# energy-management-driver-175_v2.net
KiCad netlist of a schematic drawn in EAGLE
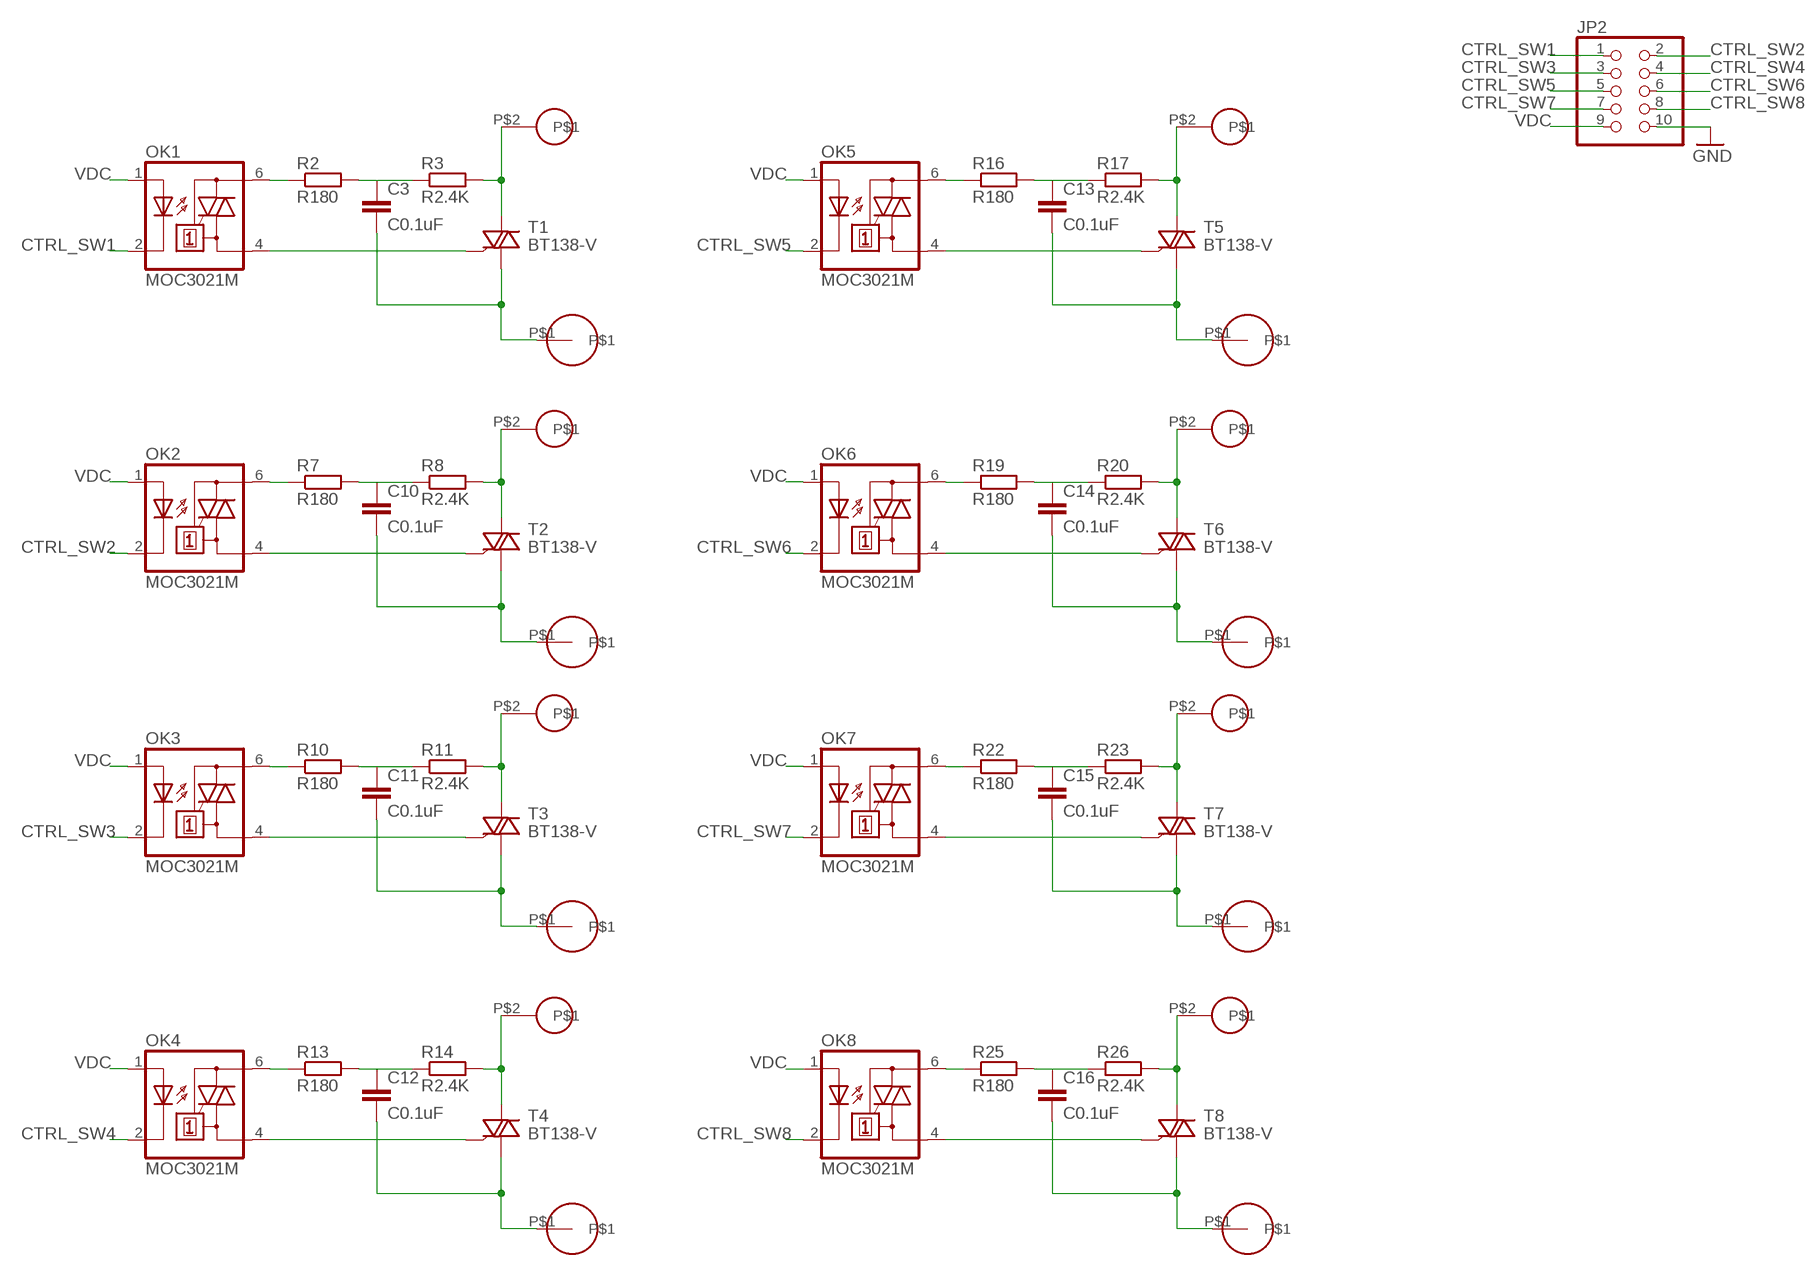
[diagram p0: schematic, sheet 1]

(export (version "E")
  (design (tool "Eeschema 10.0.6"))
  (components
    (comp (ref "C3")
      (value "C0.1uF")
      (footprint "eagle-import:C0805")
      (libsource (lib "eagle-import") (part "C-EUC0805"))
    )
    (comp (ref "C10")
      (value "C0.1uF")
      (footprint "eagle-import:C0805")
      (libsource (lib "eagle-import") (part "C-EUC0805"))
    )
    (comp (ref "C11")
      (value "C0.1uF")
      (footprint "eagle-import:C0805")
      (libsource (lib "eagle-import") (part "C-EUC0805"))
    )
    (comp (ref "C12")
      (value "C0.1uF")
      (footprint "eagle-import:C0805")
      (libsource (lib "eagle-import") (part "C-EUC0805"))
    )
    (comp (ref "C13")
      (value "C0.1uF")
      (footprint "eagle-import:C0805")
      (libsource (lib "eagle-import") (part "C-EUC0805"))
    )
    (comp (ref "C14")
      (value "C0.1uF")
      (footprint "eagle-import:C0805")
      (libsource (lib "eagle-import") (part "C-EUC0805"))
    )
    (comp (ref "C15")
      (value "C0.1uF")
      (footprint "eagle-import:C0805")
      (libsource (lib "eagle-import") (part "C-EUC0805"))
    )
    (comp (ref "C16")
      (value "C0.1uF")
      (footprint "eagle-import:C0805")
      (libsource (lib "eagle-import") (part "C-EUC0805"))
    )
    (comp (ref "JP2")
      (value "PINHD-2X5")
      (footprint "eagle-import:2X05")
      (libsource (lib "eagle-import") (part "PINHD-2X5"))
    )
    (comp (ref "OK1")
      (value "MOC3021M")
      (footprint "eagle-import:DIL06")
      (fields (field (name "MF") "FAIRCHILD SEMICONDUCTOR") (field (name "MPN") "MOC3021-M"))
      (libsource (lib "eagle-import") (part "MOC30M21"))
    )
    (comp (ref "OK2")
      (value "MOC3021M")
      (footprint "eagle-import:DIL06")
      (fields (field (name "MF") "FAIRCHILD SEMICONDUCTOR") (field (name "MPN") "MOC3021-M"))
      (libsource (lib "eagle-import") (part "MOC30M21"))
    )
    (comp (ref "OK3")
      (value "MOC3021M")
      (footprint "eagle-import:DIL06")
      (fields (field (name "MF") "FAIRCHILD SEMICONDUCTOR") (field (name "MPN") "MOC3021-M"))
      (libsource (lib "eagle-import") (part "MOC30M21"))
    )
    (comp (ref "OK4")
      (value "MOC3021M")
      (footprint "eagle-import:DIL06")
      (fields (field (name "MF") "FAIRCHILD SEMICONDUCTOR") (field (name "MPN") "MOC3021-M"))
      (libsource (lib "eagle-import") (part "MOC30M21"))
    )
    (comp (ref "OK5")
      (value "MOC3021M")
      (footprint "eagle-import:DIL06")
      (fields (field (name "MF") "FAIRCHILD SEMICONDUCTOR") (field (name "MPN") "MOC3021-M"))
      (libsource (lib "eagle-import") (part "MOC30M21"))
    )
    (comp (ref "OK6")
      (value "MOC3021M")
      (footprint "eagle-import:DIL06")
      (fields (field (name "MF") "FAIRCHILD SEMICONDUCTOR") (field (name "MPN") "MOC3021-M"))
      (libsource (lib "eagle-import") (part "MOC30M21"))
    )
    (comp (ref "OK7")
      (value "MOC3021M")
      (footprint "eagle-import:DIL06")
      (fields (field (name "MF") "FAIRCHILD SEMICONDUCTOR") (field (name "MPN") "MOC3021-M"))
      (libsource (lib "eagle-import") (part "MOC30M21"))
    )
    (comp (ref "OK8")
      (value "MOC3021M")
      (footprint "eagle-import:DIL06")
      (fields (field (name "MF") "FAIRCHILD SEMICONDUCTOR") (field (name "MPN") "MOC3021-M"))
      (libsource (lib "eagle-import") (part "MOC30M21"))
    )
    (comp (ref "R2")
      (value "R180")
      (footprint "eagle-import:M0805")
      (libsource (lib "eagle-import") (part "R-EU_M0805"))
    )
    (comp (ref "R3")
      (value "R2.4K")
      (footprint "eagle-import:M0805")
      (libsource (lib "eagle-import") (part "R-EU_M0805"))
    )
    (comp (ref "R7")
      (value "R180")
      (footprint "eagle-import:M0805")
      (libsource (lib "eagle-import") (part "R-EU_M0805"))
    )
    (comp (ref "R8")
      (value "R2.4K")
      (footprint "eagle-import:M0805")
      (libsource (lib "eagle-import") (part "R-EU_M0805"))
    )
    (comp (ref "R10")
      (value "R180")
      (footprint "eagle-import:M0805")
      (libsource (lib "eagle-import") (part "R-EU_M0805"))
    )
    (comp (ref "R11")
      (value "R2.4K")
      (footprint "eagle-import:M0805")
      (libsource (lib "eagle-import") (part "R-EU_M0805"))
    )
    (comp (ref "R13")
      (value "R180")
      (footprint "eagle-import:M0805")
      (libsource (lib "eagle-import") (part "R-EU_M0805"))
    )
    (comp (ref "R14")
      (value "R2.4K")
      (footprint "eagle-import:M0805")
      (libsource (lib "eagle-import") (part "R-EU_M0805"))
    )
    (comp (ref "R16")
      (value "R180")
      (footprint "eagle-import:M0805")
      (libsource (lib "eagle-import") (part "R-EU_M0805"))
    )
    (comp (ref "R17")
      (value "R2.4K")
      (footprint "eagle-import:M0805")
      (libsource (lib "eagle-import") (part "R-EU_M0805"))
    )
    (comp (ref "R19")
      (value "R180")
      (footprint "eagle-import:M0805")
      (libsource (lib "eagle-import") (part "R-EU_M0805"))
    )
    (comp (ref "R20")
      (value "R2.4K")
      (footprint "eagle-import:M0805")
      (libsource (lib "eagle-import") (part "R-EU_M0805"))
    )
    (comp (ref "R22")
      (value "R180")
      (footprint "eagle-import:M0805")
      (libsource (lib "eagle-import") (part "R-EU_M0805"))
    )
    (comp (ref "R23")
      (value "R2.4K")
      (footprint "eagle-import:M0805")
      (libsource (lib "eagle-import") (part "R-EU_M0805"))
    )
    (comp (ref "R25")
      (value "R180")
      (footprint "eagle-import:M0805")
      (libsource (lib "eagle-import") (part "R-EU_M0805"))
    )
    (comp (ref "R26")
      (value "R2.4K")
      (footprint "eagle-import:M0805")
      (libsource (lib "eagle-import") (part "R-EU_M0805"))
    )
    (comp (ref "T1")
      (value "BT138-V")
      (footprint "eagle-import:TO220BV")
      (libsource (lib "eagle-import") (part "BT138-V"))
    )
    (comp (ref "T2")
      (value "BT138-V")
      (footprint "eagle-import:TO220BV")
      (libsource (lib "eagle-import") (part "BT138-V"))
    )
    (comp (ref "T3")
      (value "BT138-V")
      (footprint "eagle-import:TO220BV")
      (libsource (lib "eagle-import") (part "BT138-V"))
    )
    (comp (ref "T4")
      (value "BT138-V")
      (footprint "eagle-import:TO220BV")
      (libsource (lib "eagle-import") (part "BT138-V"))
    )
    (comp (ref "T5")
      (value "BT138-V")
      (footprint "eagle-import:TO220BV")
      (libsource (lib "eagle-import") (part "BT138-V"))
    )
    (comp (ref "T6")
      (value "BT138-V")
      (footprint "eagle-import:TO220BV")
      (libsource (lib "eagle-import") (part "BT138-V"))
    )
    (comp (ref "T7")
      (value "BT138-V")
      (footprint "eagle-import:TO220BV")
      (libsource (lib "eagle-import") (part "BT138-V"))
    )
    (comp (ref "T8")
      (value "BT138-V")
      (footprint "eagle-import:TO220BV")
      (libsource (lib "eagle-import") (part "BT138-V"))
    )
    (comp (ref "U$1")
      (value "CONN-SKUN")
      (footprint "eagle-import:CONN-SKUN")
      (libsource (lib "eagle-import") (part "CONN-SKUN"))
    )
    (comp (ref "U$2")
      (value "CONN-SKUN")
      (footprint "eagle-import:CONN-SKUN")
      (libsource (lib "eagle-import") (part "CONN-SKUN"))
    )
    (comp (ref "U$3")
      (value "CONN-SKUN")
      (footprint "eagle-import:CONN-SKUN")
      (libsource (lib "eagle-import") (part "CONN-SKUN"))
    )
    (comp (ref "U$4")
      (value "CONN-SKUN")
      (footprint "eagle-import:CONN-SKUN")
      (libsource (lib "eagle-import") (part "CONN-SKUN"))
    )
    (comp (ref "U$5")
      (value "CONN-SKUN")
      (footprint "eagle-import:CONN-SKUN")
      (libsource (lib "eagle-import") (part "CONN-SKUN"))
    )
    (comp (ref "U$6")
      (value "CONN-SKUN")
      (footprint "eagle-import:CONN-SKUN")
      (libsource (lib "eagle-import") (part "CONN-SKUN"))
    )
    (comp (ref "U$7")
      (value "CONN-SKUN")
      (footprint "eagle-import:CONN-SKUN")
      (libsource (lib "eagle-import") (part "CONN-SKUN"))
    )
    (comp (ref "U$8")
      (value "CONN-SKUN")
      (footprint "eagle-import:CONN-SKUN")
      (libsource (lib "eagle-import") (part "CONN-SKUN"))
    )
    (comp (ref "U$9")
      (value "CONN-CABLE")
      (footprint "eagle-import:CONN-CABLE")
      (libsource (lib "eagle-import") (part "CONN-CABLE"))
    )
    (comp (ref "U$10")
      (value "CONN-CABLE")
      (footprint "eagle-import:CONN-CABLE")
      (libsource (lib "eagle-import") (part "CONN-CABLE"))
    )
    (comp (ref "U$11")
      (value "CONN-CABLE")
      (footprint "eagle-import:CONN-CABLE")
      (libsource (lib "eagle-import") (part "CONN-CABLE"))
    )
    (comp (ref "U$12")
      (value "CONN-CABLE")
      (footprint "eagle-import:CONN-CABLE")
      (libsource (lib "eagle-import") (part "CONN-CABLE"))
    )
    (comp (ref "U$13")
      (value "CONN-CABLE")
      (footprint "eagle-import:CONN-CABLE")
      (libsource (lib "eagle-import") (part "CONN-CABLE"))
    )
    (comp (ref "U$14")
      (value "CONN-CABLE")
      (footprint "eagle-import:CONN-CABLE")
      (libsource (lib "eagle-import") (part "CONN-CABLE"))
    )
    (comp (ref "U$15")
      (value "CONN-CABLE")
      (footprint "eagle-import:CONN-CABLE")
      (libsource (lib "eagle-import") (part "CONN-CABLE"))
    )
    (comp (ref "U$16")
      (value "CONN-CABLE")
      (footprint "eagle-import:CONN-CABLE")
      (libsource (lib "eagle-import") (part "CONN-CABLE"))
    )
  )
  (nets
    (net (code "1") (name "/CTRL_SW1") (class "Default")
      (node (ref "JP2") (pin "1") (pinfunction "1_1") (pintype "passive"))
      (node (ref "OK1") (pin "2") (pinfunction "C_2") (pintype "passive"))
    )
    (net (code "2") (name "/CTRL_SW2") (class "Default")
      (node (ref "JP2") (pin "2") (pinfunction "2_2") (pintype "passive"))
      (node (ref "OK2") (pin "2") (pinfunction "C_2") (pintype "passive"))
    )
    (net (code "3") (name "/CTRL_SW3") (class "Default")
      (node (ref "JP2") (pin "3") (pinfunction "3_3") (pintype "passive"))
      (node (ref "OK3") (pin "2") (pinfunction "C_2") (pintype "passive"))
    )
    (net (code "4") (name "/CTRL_SW4") (class "Default")
      (node (ref "JP2") (pin "4") (pinfunction "4_4") (pintype "passive"))
      (node (ref "OK4") (pin "2") (pinfunction "C_2") (pintype "passive"))
    )
    (net (code "5") (name "/CTRL_SW5") (class "Default")
      (node (ref "JP2") (pin "5") (pinfunction "5_5") (pintype "passive"))
      (node (ref "OK5") (pin "2") (pinfunction "C_2") (pintype "passive"))
    )
    (net (code "6") (name "/CTRL_SW6") (class "Default")
      (node (ref "JP2") (pin "6") (pinfunction "6_6") (pintype "passive"))
      (node (ref "OK6") (pin "2") (pinfunction "C_2") (pintype "passive"))
    )
    (net (code "7") (name "/CTRL_SW7") (class "Default")
      (node (ref "JP2") (pin "7") (pinfunction "7_7") (pintype "passive"))
      (node (ref "OK7") (pin "2") (pinfunction "C_2") (pintype "passive"))
    )
    (net (code "8") (name "/CTRL_SW8") (class "Default")
      (node (ref "JP2") (pin "8") (pinfunction "8_8") (pintype "passive"))
      (node (ref "OK8") (pin "2") (pinfunction "C_2") (pintype "passive"))
    )
    (net (code "9") (name "/VDC") (class "Default")
      (node (ref "JP2") (pin "9") (pinfunction "9_9") (pintype "passive"))
      (node (ref "OK1") (pin "1") (pinfunction "A_1") (pintype "passive"))
      (node (ref "OK2") (pin "1") (pinfunction "A_1") (pintype "passive"))
      (node (ref "OK3") (pin "1") (pinfunction "A_1") (pintype "passive"))
      (node (ref "OK4") (pin "1") (pinfunction "A_1") (pintype "passive"))
      (node (ref "OK5") (pin "1") (pinfunction "A_1") (pintype "passive"))
      (node (ref "OK6") (pin "1") (pinfunction "A_1") (pintype "passive"))
      (node (ref "OK7") (pin "1") (pinfunction "A_1") (pintype "passive"))
      (node (ref "OK8") (pin "1") (pinfunction "A_1") (pintype "passive"))
    )
    (net (code "10") (name "GND") (class "Default")
      (node (ref "JP2") (pin "10") (pinfunction "10_10") (pintype "passive"))
    )
    (net (code "11") (name "Net-(C3-Pad1)") (class "Default")
      (node (ref "C3") (pin "1") (pinfunction "1_1") (pintype "passive"))
      (node (ref "R2") (pin "2") (pinfunction "2_2") (pintype "passive"))
      (node (ref "R3") (pin "1") (pinfunction "1_1") (pintype "passive"))
    )
    (net (code "12") (name "Net-(C10-Pad1)") (class "Default")
      (node (ref "C10") (pin "1") (pinfunction "1_1") (pintype "passive"))
      (node (ref "R7") (pin "2") (pinfunction "2_2") (pintype "passive"))
      (node (ref "R8") (pin "1") (pinfunction "1_1") (pintype "passive"))
    )
    (net (code "13") (name "Net-(C11-Pad1)") (class "Default")
      (node (ref "C11") (pin "1") (pinfunction "1_1") (pintype "passive"))
      (node (ref "R10") (pin "2") (pinfunction "2_2") (pintype "passive"))
      (node (ref "R11") (pin "1") (pinfunction "1_1") (pintype "passive"))
    )
    (net (code "14") (name "Net-(C12-Pad1)") (class "Default")
      (node (ref "C12") (pin "1") (pinfunction "1_1") (pintype "passive"))
      (node (ref "R13") (pin "2") (pinfunction "2_2") (pintype "passive"))
      (node (ref "R14") (pin "1") (pinfunction "1_1") (pintype "passive"))
    )
    (net (code "15") (name "Net-(C13-Pad1)") (class "Default")
      (node (ref "C13") (pin "1") (pinfunction "1_1") (pintype "passive"))
      (node (ref "R16") (pin "2") (pinfunction "2_2") (pintype "passive"))
      (node (ref "R17") (pin "1") (pinfunction "1_1") (pintype "passive"))
    )
    (net (code "16") (name "Net-(C14-Pad1)") (class "Default")
      (node (ref "C14") (pin "1") (pinfunction "1_1") (pintype "passive"))
      (node (ref "R19") (pin "2") (pinfunction "2_2") (pintype "passive"))
      (node (ref "R20") (pin "1") (pinfunction "1_1") (pintype "passive"))
    )
    (net (code "17") (name "Net-(C15-Pad1)") (class "Default")
      (node (ref "C15") (pin "1") (pinfunction "1_1") (pintype "passive"))
      (node (ref "R22") (pin "2") (pinfunction "2_2") (pintype "passive"))
      (node (ref "R23") (pin "1") (pinfunction "1_1") (pintype "passive"))
    )
    (net (code "18") (name "Net-(C16-Pad1)") (class "Default")
      (node (ref "C16") (pin "1") (pinfunction "1_1") (pintype "passive"))
      (node (ref "R25") (pin "2") (pinfunction "2_2") (pintype "passive"))
      (node (ref "R26") (pin "1") (pinfunction "1_1") (pintype "passive"))
    )
    (net (code "19") (name "Net-(OK1-A1)") (class "Default")
      (node (ref "OK1") (pin "4") (pinfunction "A1_4") (pintype "passive"))
      (node (ref "T1") (pin "G") (pinfunction "G_G") (pintype "passive"))
    )
    (net (code "20") (name "Net-(OK1-A2)") (class "Default")
      (node (ref "OK1") (pin "6") (pinfunction "A2_6") (pintype "passive"))
      (node (ref "R2") (pin "1") (pinfunction "1_1") (pintype "passive"))
    )
    (net (code "21") (name "Net-(OK2-A1)") (class "Default")
      (node (ref "OK2") (pin "4") (pinfunction "A1_4") (pintype "passive"))
      (node (ref "T2") (pin "G") (pinfunction "G_G") (pintype "passive"))
    )
    (net (code "22") (name "Net-(OK2-A2)") (class "Default")
      (node (ref "OK2") (pin "6") (pinfunction "A2_6") (pintype "passive"))
      (node (ref "R7") (pin "1") (pinfunction "1_1") (pintype "passive"))
    )
    (net (code "23") (name "Net-(OK3-A1)") (class "Default")
      (node (ref "OK3") (pin "4") (pinfunction "A1_4") (pintype "passive"))
      (node (ref "T3") (pin "G") (pinfunction "G_G") (pintype "passive"))
    )
    (net (code "24") (name "Net-(OK3-A2)") (class "Default")
      (node (ref "OK3") (pin "6") (pinfunction "A2_6") (pintype "passive"))
      (node (ref "R10") (pin "1") (pinfunction "1_1") (pintype "passive"))
    )
    (net (code "25") (name "Net-(OK4-A1)") (class "Default")
      (node (ref "OK4") (pin "4") (pinfunction "A1_4") (pintype "passive"))
      (node (ref "T4") (pin "G") (pinfunction "G_G") (pintype "passive"))
    )
    (net (code "26") (name "Net-(OK4-A2)") (class "Default")
      (node (ref "OK4") (pin "6") (pinfunction "A2_6") (pintype "passive"))
      (node (ref "R13") (pin "1") (pinfunction "1_1") (pintype "passive"))
    )
    (net (code "27") (name "Net-(OK5-A1)") (class "Default")
      (node (ref "OK5") (pin "4") (pinfunction "A1_4") (pintype "passive"))
      (node (ref "T5") (pin "G") (pinfunction "G_G") (pintype "passive"))
    )
    (net (code "28") (name "Net-(OK5-A2)") (class "Default")
      (node (ref "OK5") (pin "6") (pinfunction "A2_6") (pintype "passive"))
      (node (ref "R16") (pin "1") (pinfunction "1_1") (pintype "passive"))
    )
    (net (code "29") (name "Net-(OK6-A1)") (class "Default")
      (node (ref "OK6") (pin "4") (pinfunction "A1_4") (pintype "passive"))
      (node (ref "T6") (pin "G") (pinfunction "G_G") (pintype "passive"))
    )
    (net (code "30") (name "Net-(OK6-A2)") (class "Default")
      (node (ref "OK6") (pin "6") (pinfunction "A2_6") (pintype "passive"))
      (node (ref "R19") (pin "1") (pinfunction "1_1") (pintype "passive"))
    )
    (net (code "31") (name "Net-(OK7-A1)") (class "Default")
      (node (ref "OK7") (pin "4") (pinfunction "A1_4") (pintype "passive"))
      (node (ref "T7") (pin "G") (pinfunction "G_G") (pintype "passive"))
    )
    (net (code "32") (name "Net-(OK7-A2)") (class "Default")
      (node (ref "OK7") (pin "6") (pinfunction "A2_6") (pintype "passive"))
      (node (ref "R22") (pin "1") (pinfunction "1_1") (pintype "passive"))
    )
    (net (code "33") (name "Net-(OK8-A1)") (class "Default")
      (node (ref "OK8") (pin "4") (pinfunction "A1_4") (pintype "passive"))
      (node (ref "T8") (pin "G") (pinfunction "G_G") (pintype "passive"))
    )
    (net (code "34") (name "Net-(OK8-A2)") (class "Default")
      (node (ref "OK8") (pin "6") (pinfunction "A2_6") (pintype "passive"))
      (node (ref "R25") (pin "1") (pinfunction "1_1") (pintype "passive"))
    )
    (net (code "35") (name "Net-(T1-A1)") (class "Default")
      (node (ref "C3") (pin "2") (pinfunction "2_2") (pintype "passive"))
      (node (ref "T1") (pin "T1") (pinfunction "A1_T1") (pintype "passive"))
      (node (ref "U$9") (pin "P$1") (pinfunction "P$1_P$1") (pintype "bidirectional"))
    )
    (net (code "36") (name "Net-(T1-A2)") (class "Default")
      (node (ref "R3") (pin "2") (pinfunction "2_2") (pintype "passive"))
      (node (ref "T1") (pin "T2") (pinfunction "A2_T2") (pintype "passive"))
      (node (ref "U$1") (pin "P$2") (pinfunction "P$1_P$2") (pintype "bidirectional"))
    )
    (net (code "37") (name "Net-(T2-A1)") (class "Default")
      (node (ref "C10") (pin "2") (pinfunction "2_2") (pintype "passive"))
      (node (ref "T2") (pin "T1") (pinfunction "A1_T1") (pintype "passive"))
      (node (ref "U$11") (pin "P$1") (pinfunction "P$1_P$1") (pintype "bidirectional"))
    )
    (net (code "38") (name "Net-(T2-A2)") (class "Default")
      (node (ref "R8") (pin "2") (pinfunction "2_2") (pintype "passive"))
      (node (ref "T2") (pin "T2") (pinfunction "A2_T2") (pintype "passive"))
      (node (ref "U$2") (pin "P$2") (pinfunction "P$1_P$2") (pintype "bidirectional"))
    )
    (net (code "39") (name "Net-(T3-A1)") (class "Default")
      (node (ref "C11") (pin "2") (pinfunction "2_2") (pintype "passive"))
      (node (ref "T3") (pin "T1") (pinfunction "A1_T1") (pintype "passive"))
      (node (ref "U$14") (pin "P$1") (pinfunction "P$1_P$1") (pintype "bidirectional"))
    )
    (net (code "40") (name "Net-(T3-A2)") (class "Default")
      (node (ref "R11") (pin "2") (pinfunction "2_2") (pintype "passive"))
      (node (ref "T3") (pin "T2") (pinfunction "A2_T2") (pintype "passive"))
      (node (ref "U$3") (pin "P$2") (pinfunction "P$1_P$2") (pintype "bidirectional"))
    )
    (net (code "41") (name "Net-(T4-A1)") (class "Default")
      (node (ref "C12") (pin "2") (pinfunction "2_2") (pintype "passive"))
      (node (ref "T4") (pin "T1") (pinfunction "A1_T1") (pintype "passive"))
      (node (ref "U$13") (pin "P$1") (pinfunction "P$1_P$1") (pintype "bidirectional"))
    )
    (net (code "42") (name "Net-(T4-A2)") (class "Default")
      (node (ref "R14") (pin "2") (pinfunction "2_2") (pintype "passive"))
      (node (ref "T4") (pin "T2") (pinfunction "A2_T2") (pintype "passive"))
      (node (ref "U$4") (pin "P$2") (pinfunction "P$1_P$2") (pintype "bidirectional"))
    )
    (net (code "43") (name "Net-(T5-A1)") (class "Default")
      (node (ref "C13") (pin "2") (pinfunction "2_2") (pintype "passive"))
      (node (ref "T5") (pin "T1") (pinfunction "A1_T1") (pintype "passive"))
      (node (ref "U$10") (pin "P$1") (pinfunction "P$1_P$1") (pintype "bidirectional"))
    )
    (net (code "44") (name "Net-(T5-A2)") (class "Default")
      (node (ref "R17") (pin "2") (pinfunction "2_2") (pintype "passive"))
      (node (ref "T5") (pin "T2") (pinfunction "A2_T2") (pintype "passive"))
      (node (ref "U$8") (pin "P$2") (pinfunction "P$1_P$2") (pintype "bidirectional"))
    )
    (net (code "45") (name "Net-(T6-A1)") (class "Default")
      (node (ref "C14") (pin "2") (pinfunction "2_2") (pintype "passive"))
      (node (ref "T6") (pin "T1") (pinfunction "A1_T1") (pintype "passive"))
      (node (ref "U$12") (pin "P$1") (pinfunction "P$1_P$1") (pintype "bidirectional"))
    )
    (net (code "46") (name "Net-(T6-A2)") (class "Default")
      (node (ref "R20") (pin "2") (pinfunction "2_2") (pintype "passive"))
      (node (ref "T6") (pin "T2") (pinfunction "A2_T2") (pintype "passive"))
      (node (ref "U$7") (pin "P$2") (pinfunction "P$1_P$2") (pintype "bidirectional"))
    )
    (net (code "47") (name "Net-(T7-A1)") (class "Default")
      (node (ref "C15") (pin "2") (pinfunction "2_2") (pintype "passive"))
      (node (ref "T7") (pin "T1") (pinfunction "A1_T1") (pintype "passive"))
      (node (ref "U$15") (pin "P$1") (pinfunction "P$1_P$1") (pintype "bidirectional"))
    )
    (net (code "48") (name "Net-(T7-A2)") (class "Default")
      (node (ref "R23") (pin "2") (pinfunction "2_2") (pintype "passive"))
      (node (ref "T7") (pin "T2") (pinfunction "A2_T2") (pintype "passive"))
      (node (ref "U$6") (pin "P$2") (pinfunction "P$1_P$2") (pintype "bidirectional"))
    )
    (net (code "49") (name "Net-(T8-A1)") (class "Default")
      (node (ref "C16") (pin "2") (pinfunction "2_2") (pintype "passive"))
      (node (ref "T8") (pin "T1") (pinfunction "A1_T1") (pintype "passive"))
      (node (ref "U$16") (pin "P$1") (pinfunction "P$1_P$1") (pintype "bidirectional"))
    )
    (net (code "50") (name "Net-(T8-A2)") (class "Default")
      (node (ref "R26") (pin "2") (pinfunction "2_2") (pintype "passive"))
      (node (ref "T8") (pin "T2") (pinfunction "A2_T2") (pintype "passive"))
      (node (ref "U$5") (pin "P$2") (pinfunction "P$1_P$2") (pintype "bidirectional"))
    )
  )
)
